# M402B.net
KiCad netlist of a schematic drawn in EAGLE
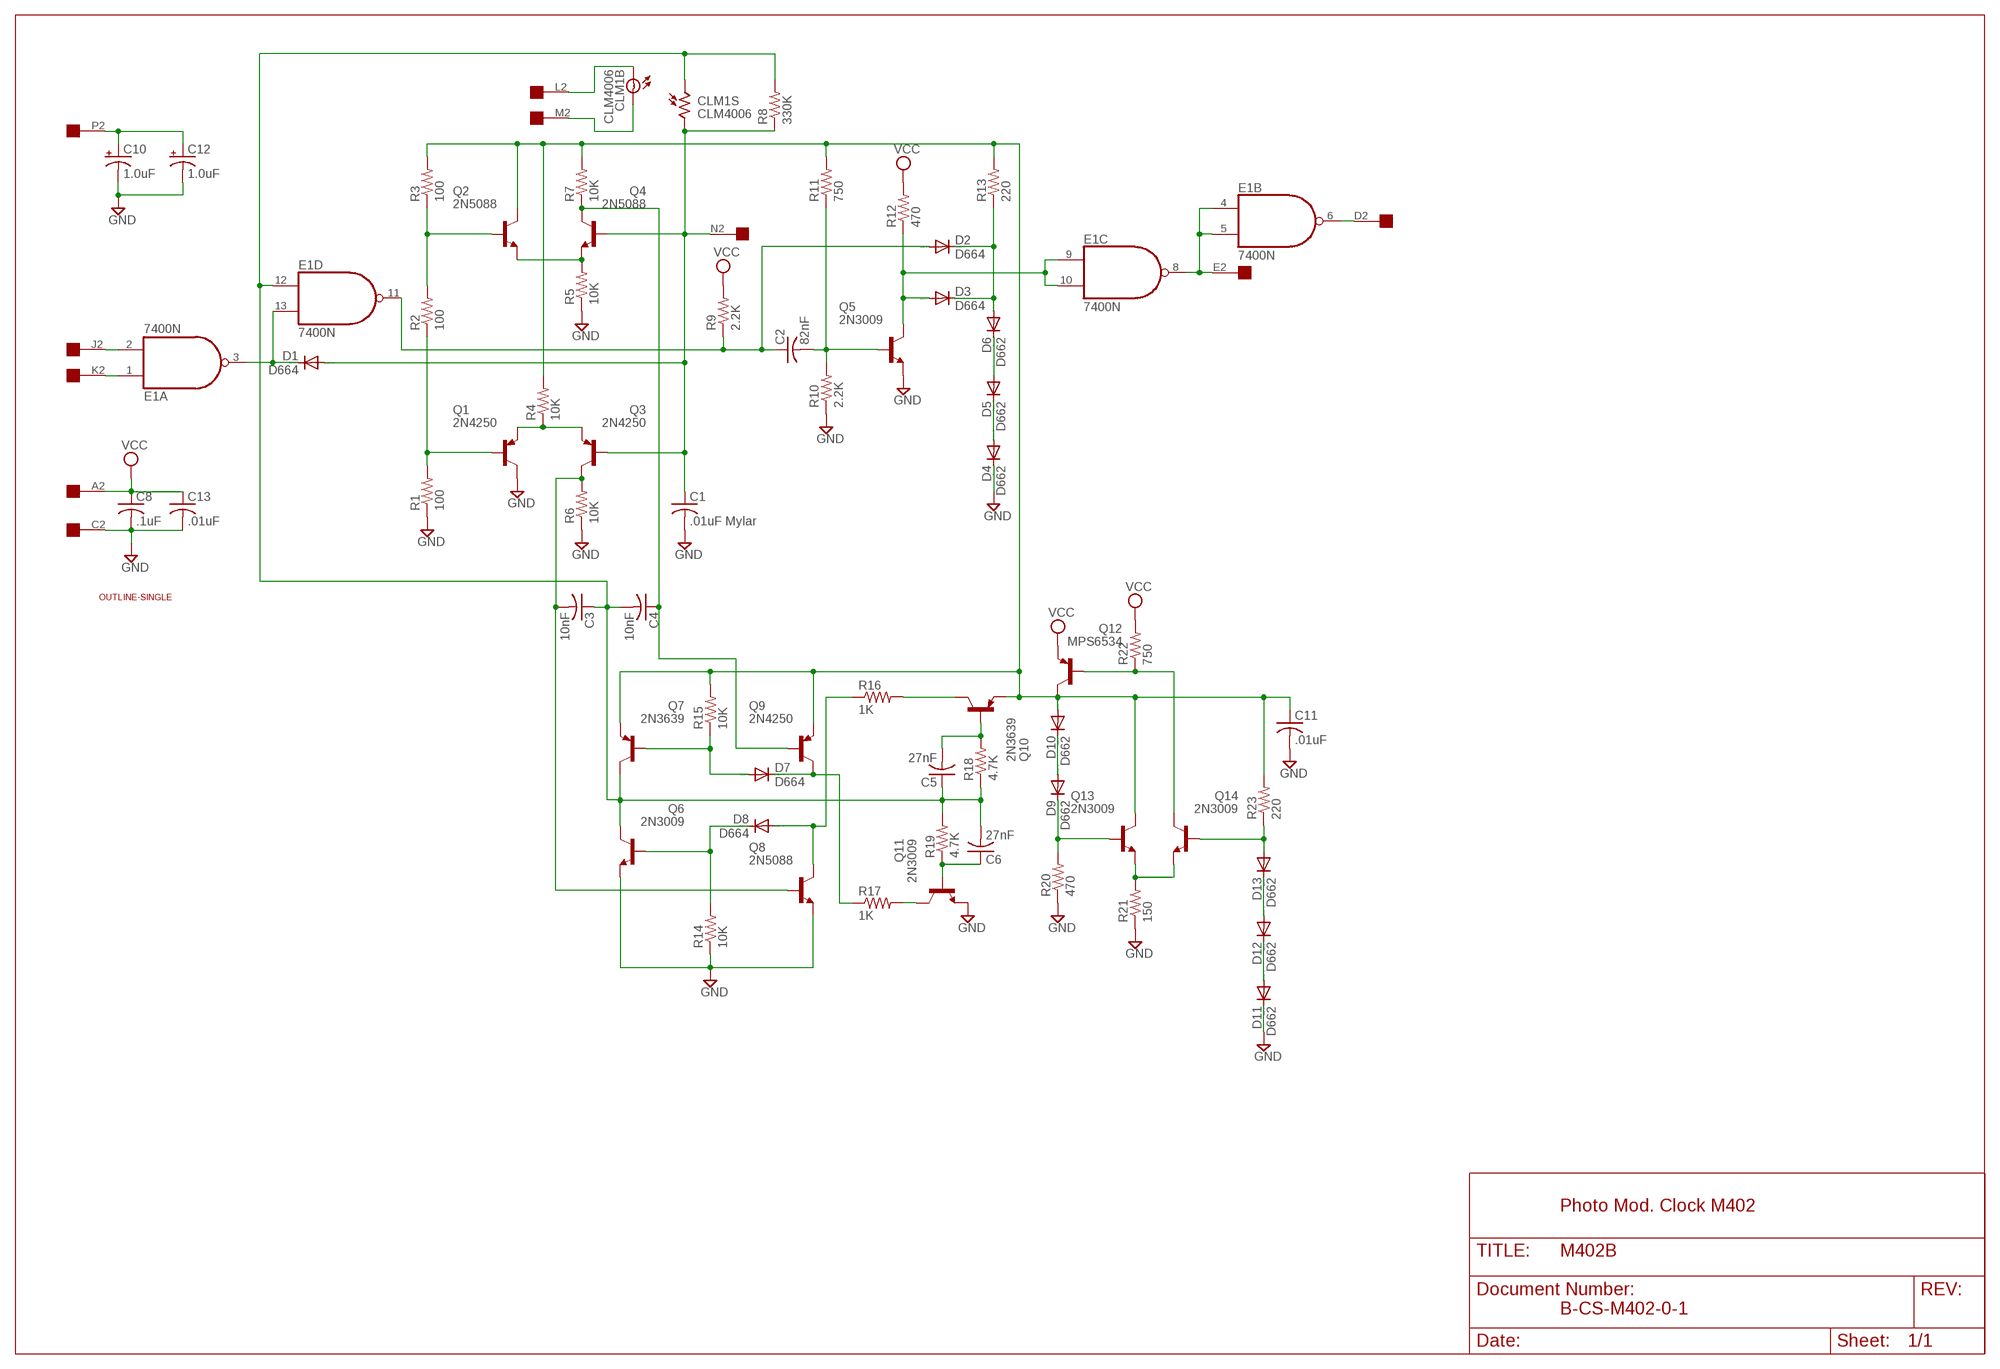
[diagram p0: schematic, sheet 1]

(export (version "E")
  (design (tool "Eeschema 10.0.6"))
  (components
    (comp (ref "C1")
      (value ".01uF Mylar")
      (footprint "eagle-import:C225-062X268")
      (libsource (lib "eagle-import") (part "C-US225-062X268"))
    )
    (comp (ref "C2")
      (value "82nF")
      (footprint "eagle-import:C050-025X075")
      (libsource (lib "eagle-import") (part "C-US050-025X075"))
    )
    (comp (ref "C3")
      (value "10nF")
      (footprint "eagle-import:C075-032X103")
      (libsource (lib "eagle-import") (part "C-US075-032X103"))
    )
    (comp (ref "C4")
      (value "10nF")
      (footprint "eagle-import:C075-032X103")
      (libsource (lib "eagle-import") (part "C-US075-032X103"))
    )
    (comp (ref "C5")
      (value "27nF")
      (footprint "eagle-import:C075-032X103")
      (libsource (lib "eagle-import") (part "C-US075-032X103"))
    )
    (comp (ref "C6")
      (value "27nF")
      (footprint "eagle-import:C075-032X103")
      (libsource (lib "eagle-import") (part "C-US075-032X103"))
    )
    (comp (ref "C8")
      (value ".1uF")
      (footprint "eagle-import:C075-032X103")
      (libsource (lib "eagle-import") (part "C-US075-032X103"))
    )
    (comp (ref "C10")
      (value "1.0uF")
      (footprint "eagle-import:E15-5")
      (libsource (lib "eagle-import") (part "CPOL-USE15-5AXIAL"))
    )
    (comp (ref "C11")
      (value ".01uF")
      (footprint "eagle-import:C050-025X075")
      (libsource (lib "eagle-import") (part "C-US050-025X075"))
    )
    (comp (ref "C12")
      (value "1.0uF")
      (footprint "eagle-import:E15-5")
      (libsource (lib "eagle-import") (part "CPOL-USE15-5AXIAL"))
    )
    (comp (ref "C13")
      (value ".01uF")
      (footprint "eagle-import:C102-043X133")
      (libsource (lib "eagle-import") (part "C-US102-043X133"))
    )
    (comp (ref "CLM1")
      (value "CLM4006")
      (footprint "eagle-import:CLM4006")
      (libsource (lib "eagle-import") (part "CLM4006"))
    )
    (comp (ref "D1")
      (value "D664")
      (footprint "eagle-import:DO35-10")
      (libsource (lib "eagle-import") (part "DIODE-DO35-10"))
    )
    (comp (ref "D2")
      (value "D664")
      (footprint "eagle-import:DO35-10")
      (libsource (lib "eagle-import") (part "DIODE-DO35-10"))
    )
    (comp (ref "D3")
      (value "D664")
      (footprint "eagle-import:DO35-10")
      (libsource (lib "eagle-import") (part "DIODE-DO35-10"))
    )
    (comp (ref "D4")
      (value "D662")
      (footprint "eagle-import:DO35-10")
      (libsource (lib "eagle-import") (part "DIODE-DO35-10"))
    )
    (comp (ref "D5")
      (value "D662")
      (footprint "eagle-import:DO35-10")
      (libsource (lib "eagle-import") (part "DIODE-DO35-10"))
    )
    (comp (ref "D6")
      (value "D662")
      (footprint "eagle-import:DO35-10")
      (libsource (lib "eagle-import") (part "DIODE-DO35-10"))
    )
    (comp (ref "D7")
      (value "D664")
      (footprint "eagle-import:DO35-10")
      (libsource (lib "eagle-import") (part "DIODE-DO35-10"))
    )
    (comp (ref "D8")
      (value "D664")
      (footprint "eagle-import:DO35-10")
      (libsource (lib "eagle-import") (part "DIODE-DO35-10"))
    )
    (comp (ref "D9")
      (value "D662")
      (footprint "eagle-import:DO35-10")
      (libsource (lib "eagle-import") (part "DIODE-DO35-10"))
    )
    (comp (ref "D10")
      (value "D662")
      (footprint "eagle-import:DO35-10")
      (libsource (lib "eagle-import") (part "DIODE-DO35-10"))
    )
    (comp (ref "D11")
      (value "D662")
      (footprint "eagle-import:DO35-10")
      (libsource (lib "eagle-import") (part "DIODE-DO35-10"))
    )
    (comp (ref "D12")
      (value "D662")
      (footprint "eagle-import:DO35-10")
      (libsource (lib "eagle-import") (part "DIODE-DO35-10"))
    )
    (comp (ref "D13")
      (value "D662")
      (footprint "eagle-import:DO35-10")
      (libsource (lib "eagle-import") (part "DIODE-DO35-10"))
    )
    (comp (ref "E1")
      (value "7400N")
      (footprint "eagle-import:DIL14")
      (libsource (lib "eagle-import") (part "7400N"))
    )
    (comp (ref "Q1")
      (value "2N4250")
      (footprint "eagle-import:TO5")
      (libsource (lib "eagle-import") (part "-PNP-TO5"))
    )
    (comp (ref "Q2")
      (value "2N5088")
      (footprint "eagle-import:TO5")
      (libsource (lib "eagle-import") (part "-NPN-TO5"))
    )
    (comp (ref "Q3")
      (value "2N4250")
      (footprint "eagle-import:TO5")
      (libsource (lib "eagle-import") (part "-PNP-TO5"))
    )
    (comp (ref "Q4")
      (value "2N5088")
      (footprint "eagle-import:TO5")
      (libsource (lib "eagle-import") (part "-NPN-TO5"))
    )
    (comp (ref "Q5")
      (value "2N3009")
      (footprint "eagle-import:TO5")
      (libsource (lib "eagle-import") (part "-NPN-TO5"))
    )
    (comp (ref "Q6")
      (value "2N3009")
      (footprint "eagle-import:TO5")
      (libsource (lib "eagle-import") (part "-NPN-TO5"))
    )
    (comp (ref "Q7")
      (value "2N3639")
      (footprint "eagle-import:TO5")
      (libsource (lib "eagle-import") (part "-PNP-TO5"))
    )
    (comp (ref "Q8")
      (value "2N5088")
      (footprint "eagle-import:TO5")
      (libsource (lib "eagle-import") (part "-NPN-TO5"))
    )
    (comp (ref "Q9")
      (value "2N4250")
      (footprint "eagle-import:TO5")
      (libsource (lib "eagle-import") (part "-PNP-TO5"))
    )
    (comp (ref "Q10")
      (value "2N3639")
      (footprint "eagle-import:TO5")
      (libsource (lib "eagle-import") (part "-PNP-TO5"))
    )
    (comp (ref "Q11")
      (value "2N3009")
      (footprint "eagle-import:TO5")
      (libsource (lib "eagle-import") (part "-NPN-TO5"))
    )
    (comp (ref "Q12")
      (value "MPS6534")
      (footprint "eagle-import:TO5")
      (libsource (lib "eagle-import") (part "-PNP-TO5"))
    )
    (comp (ref "Q13")
      (value "2N3009")
      (footprint "eagle-import:TO5")
      (libsource (lib "eagle-import") (part "-NPN-TO5"))
    )
    (comp (ref "Q14")
      (value "2N3009")
      (footprint "eagle-import:TO5")
      (libsource (lib "eagle-import") (part "-NPN-TO5"))
    )
    (comp (ref "R1")
      (value "100")
      (footprint "eagle-import:0207_10")
      (libsource (lib "eagle-import") (part "R-US_0207/10"))
    )
    (comp (ref "R2")
      (value "100")
      (footprint "eagle-import:0207_10")
      (libsource (lib "eagle-import") (part "R-US_0207/10"))
    )
    (comp (ref "R3")
      (value "100")
      (footprint "eagle-import:0207_10")
      (libsource (lib "eagle-import") (part "R-US_0207/10"))
    )
    (comp (ref "R4")
      (value "10K")
      (footprint "eagle-import:0207_10")
      (libsource (lib "eagle-import") (part "R-US_0207/10"))
    )
    (comp (ref "R5")
      (value "10K")
      (footprint "eagle-import:0207_10")
      (libsource (lib "eagle-import") (part "R-US_0207/10"))
    )
    (comp (ref "R6")
      (value "10K")
      (footprint "eagle-import:0207_10")
      (libsource (lib "eagle-import") (part "R-US_0207/10"))
    )
    (comp (ref "R7")
      (value "10K")
      (footprint "eagle-import:0207_10")
      (libsource (lib "eagle-import") (part "R-US_0207/10"))
    )
    (comp (ref "R8")
      (value "330K")
      (footprint "eagle-import:0207_10")
      (libsource (lib "eagle-import") (part "R-US_0207/10"))
    )
    (comp (ref "R9")
      (value "2.2K")
      (footprint "eagle-import:0207_10")
      (libsource (lib "eagle-import") (part "R-US_0207/10"))
    )
    (comp (ref "R10")
      (value "2.2K")
      (footprint "eagle-import:0207_10")
      (libsource (lib "eagle-import") (part "R-US_0207/10"))
    )
    (comp (ref "R11")
      (value "750")
      (footprint "eagle-import:0207_10")
      (libsource (lib "eagle-import") (part "R-US_0207/10"))
    )
    (comp (ref "R12")
      (value "470")
      (footprint "eagle-import:0207_10")
      (libsource (lib "eagle-import") (part "R-US_0207/10"))
    )
    (comp (ref "R13")
      (value "220")
      (footprint "eagle-import:0207_10")
      (libsource (lib "eagle-import") (part "R-US_0207/10"))
    )
    (comp (ref "R14")
      (value "10K")
      (footprint "eagle-import:0207_10")
      (libsource (lib "eagle-import") (part "R-US_0207/10"))
    )
    (comp (ref "R15")
      (value "10K")
      (footprint "eagle-import:0207_10")
      (libsource (lib "eagle-import") (part "R-US_0207/10"))
    )
    (comp (ref "R16")
      (value "1K")
      (footprint "eagle-import:0207_10")
      (libsource (lib "eagle-import") (part "R-US_0207/10"))
    )
    (comp (ref "R17")
      (value "1K")
      (footprint "eagle-import:0207_10")
      (libsource (lib "eagle-import") (part "R-US_0207/10"))
    )
    (comp (ref "R18")
      (value "4.7K")
      (footprint "eagle-import:0207_10")
      (libsource (lib "eagle-import") (part "R-US_0207/10"))
    )
    (comp (ref "R19")
      (value "4.7K")
      (footprint "eagle-import:0207_10")
      (libsource (lib "eagle-import") (part "R-US_0207/10"))
    )
    (comp (ref "R20")
      (value "470")
      (footprint "eagle-import:0207_10")
      (libsource (lib "eagle-import") (part "R-US_0207/10"))
    )
    (comp (ref "R21")
      (value "150")
      (footprint "eagle-import:0207_10")
      (libsource (lib "eagle-import") (part "R-US_0207/10"))
    )
    (comp (ref "R22")
      (value "750")
      (footprint "eagle-import:0207_10")
      (libsource (lib "eagle-import") (part "R-US_0207/10"))
    )
    (comp (ref "R23")
      (value "220")
      (footprint "eagle-import:0207_10")
      (libsource (lib "eagle-import") (part "R-US_0207/10"))
    )
    (comp (ref "U$1")
      (value "OUTLINE-SINGLE")
      (footprint "eagle-import:SINGLE")
      (libsource (lib "eagle-import") (part "OUTLINE-SINGLE"))
    )
    (comp (ref "U$3")
      (value "EDGE-1")
      (footprint "eagle-import:EDGE-CON1")
      (libsource (lib "eagle-import") (part "EDGE-1"))
    )
  )
  (nets
    (net (code "1") (name "GND") (class "Default")
      (node (ref "C1") (pin "2") (pinfunction "2_2") (pintype "passive"))
      (node (ref "C10") (pin "-") (pinfunction "-_-") (pintype "passive"))
      (node (ref "C11") (pin "2") (pinfunction "2_2") (pintype "passive"))
      (node (ref "C12") (pin "-") (pinfunction "-_-") (pintype "passive"))
      (node (ref "C13") (pin "2") (pinfunction "2_2") (pintype "passive"))
      (node (ref "C8") (pin "2") (pinfunction "2_2") (pintype "passive"))
      (node (ref "D11") (pin "C") (pinfunction "C_C") (pintype "passive"))
      (node (ref "D4") (pin "C") (pinfunction "C_C") (pintype "passive"))
      (node (ref "Q1") (pin "3") (pinfunction "C_3") (pintype "passive"))
      (node (ref "Q11") (pin "1") (pinfunction "E_1") (pintype "passive"))
      (node (ref "Q5") (pin "1") (pinfunction "E_1") (pintype "passive"))
      (node (ref "Q6") (pin "1") (pinfunction "E_1") (pintype "passive"))
      (node (ref "Q8") (pin "1") (pinfunction "E_1") (pintype "passive"))
      (node (ref "R1") (pin "1") (pinfunction "1_1") (pintype "passive"))
      (node (ref "R10") (pin "1") (pinfunction "1_1") (pintype "passive"))
      (node (ref "R14") (pin "1") (pinfunction "1_1") (pintype "passive"))
      (node (ref "R20") (pin "1") (pinfunction "1_1") (pintype "passive"))
      (node (ref "R21") (pin "1") (pinfunction "1_1") (pintype "passive"))
      (node (ref "R5") (pin "1") (pinfunction "1_1") (pintype "passive"))
      (node (ref "R6") (pin "1") (pinfunction "1_1") (pintype "passive"))
      (node (ref "U$3") (pin "C2") (pinfunction "1_C2") (pintype "bidirectional"))
    )
    (net (code "2") (name "Net-(CLM1A-A)") (class "Default")
      (node (ref "CLM1") (pin "B1") (pinfunction "A_B1") (pintype "passive"))
      (node (ref "U$3") (pin "M2") (pinfunction "1_M2") (pintype "bidirectional"))
    )
    (net (code "3") (name "Net-(CLM1A-B)") (class "Default")
      (node (ref "CLM1") (pin "B2") (pinfunction "B_B2") (pintype "passive"))
      (node (ref "U$3") (pin "L2") (pinfunction "1_L2") (pintype "bidirectional"))
    )
    (net (code "4") (name "Net-(CLM1B-1)") (class "Default")
      (node (ref "C3") (pin "1") (pinfunction "1_1") (pintype "passive"))
      (node (ref "C4") (pin "2") (pinfunction "2_2") (pintype "passive"))
      (node (ref "C5") (pin "1") (pinfunction "1_1") (pintype "passive"))
      (node (ref "C6") (pin "2") (pinfunction "2_2") (pintype "passive"))
      (node (ref "CLM1") (pin "S1") (pinfunction "1_S1") (pintype "passive"))
      (node (ref "E1") (pin "12") (pinfunction "I0_12") (pintype "input"))
      (node (ref "Q6") (pin "3") (pinfunction "C_3") (pintype "passive"))
      (node (ref "Q7") (pin "3") (pinfunction "C_3") (pintype "passive"))
      (node (ref "R18") (pin "1") (pinfunction "1_1") (pintype "passive"))
      (node (ref "R19") (pin "2") (pinfunction "2_2") (pintype "passive"))
      (node (ref "R8") (pin "2") (pinfunction "2_2") (pintype "passive"))
    )
    (net (code "5") (name "Net-(CLM1B-2)") (class "Default")
      (node (ref "C1") (pin "1") (pinfunction "1_1") (pintype "passive"))
      (node (ref "CLM1") (pin "S2") (pinfunction "2_S2") (pintype "passive"))
      (node (ref "D1") (pin "A") (pinfunction "A_A") (pintype "passive"))
      (node (ref "Q3") (pin "2") (pinfunction "B_2") (pintype "passive"))
      (node (ref "Q4") (pin "2") (pinfunction "B_2") (pintype "passive"))
      (node (ref "R8") (pin "1") (pinfunction "1_1") (pintype "passive"))
      (node (ref "U$3") (pin "N2") (pinfunction "1_N2") (pintype "bidirectional"))
    )
    (net (code "6") (name "Net-(D2-PadC)") (class "Default")
      (node (ref "D2") (pin "C") (pinfunction "C_C") (pintype "passive"))
      (node (ref "D3") (pin "C") (pinfunction "C_C") (pintype "passive"))
      (node (ref "D6") (pin "A") (pinfunction "A_A") (pintype "passive"))
      (node (ref "R13") (pin "1") (pinfunction "1_1") (pintype "passive"))
    )
    (net (code "7") (name "Net-(D4-PadA)") (class "Default")
      (node (ref "D4") (pin "A") (pinfunction "A_A") (pintype "passive"))
      (node (ref "D5") (pin "C") (pinfunction "C_C") (pintype "passive"))
    )
    (net (code "8") (name "Net-(D5-PadA)") (class "Default")
      (node (ref "D5") (pin "A") (pinfunction "A_A") (pintype "passive"))
      (node (ref "D6") (pin "C") (pinfunction "C_C") (pintype "passive"))
    )
    (net (code "9") (name "Net-(D10-PadC)") (class "Default")
      (node (ref "D10") (pin "C") (pinfunction "C_C") (pintype "passive"))
      (node (ref "D9") (pin "A") (pinfunction "A_A") (pintype "passive"))
    )
    (net (code "10") (name "Net-(D11-PadA)") (class "Default")
      (node (ref "D11") (pin "A") (pinfunction "A_A") (pintype "passive"))
      (node (ref "D12") (pin "C") (pinfunction "C_C") (pintype "passive"))
    )
    (net (code "11") (name "Net-(D12-PadA)") (class "Default")
      (node (ref "D12") (pin "A") (pinfunction "A_A") (pintype "passive"))
      (node (ref "D13") (pin "C") (pinfunction "C_C") (pintype "passive"))
    )
    (net (code "12") (name "Net-(E1A-I0)") (class "Default")
      (node (ref "E1") (pin "1") (pinfunction "I0_1") (pintype "input"))
      (node (ref "U$3") (pin "K2") (pinfunction "1_K2") (pintype "bidirectional"))
    )
    (net (code "13") (name "Net-(E1A-I1)") (class "Default")
      (node (ref "E1") (pin "2") (pinfunction "I1_2") (pintype "input"))
      (node (ref "U$3") (pin "J2") (pinfunction "1_J2") (pintype "bidirectional"))
    )
    (net (code "14") (name "Net-(E1A-O)") (class "Default")
      (node (ref "D1") (pin "C") (pinfunction "C_C") (pintype "passive"))
      (node (ref "E1") (pin "13") (pinfunction "I1_13") (pintype "input"))
      (node (ref "E1") (pin "3") (pinfunction "O_3") (pintype "output"))
    )
    (net (code "15") (name "Net-(E1B-I0)") (class "Default")
      (node (ref "E1") (pin "4") (pinfunction "I0_4") (pintype "input"))
      (node (ref "E1") (pin "5") (pinfunction "I1_5") (pintype "input"))
      (node (ref "E1") (pin "8") (pinfunction "O_8") (pintype "output"))
      (node (ref "U$3") (pin "E2") (pinfunction "1_E2") (pintype "bidirectional"))
    )
    (net (code "16") (name "Net-(E1B-O)") (class "Default")
      (node (ref "E1") (pin "6") (pinfunction "O_6") (pintype "output"))
      (node (ref "U$3") (pin "D2") (pinfunction "1_D2") (pintype "bidirectional"))
    )
    (net (code "17") (name "Net-(E1C-I0)") (class "Default")
      (node (ref "D3") (pin "A") (pinfunction "A_A") (pintype "passive"))
      (node (ref "E1") (pin "10") (pinfunction "I1_10") (pintype "input"))
      (node (ref "E1") (pin "9") (pinfunction "I0_9") (pintype "input"))
      (node (ref "Q5") (pin "3") (pinfunction "C_3") (pintype "passive"))
      (node (ref "R12") (pin "1") (pinfunction "1_1") (pintype "passive"))
    )
    (net (code "18") (name "Net-(E1D-O)") (class "Default")
      (node (ref "C2") (pin "1") (pinfunction "1_1") (pintype "passive"))
      (node (ref "D2") (pin "A") (pinfunction "A_A") (pintype "passive"))
      (node (ref "E1") (pin "11") (pinfunction "O_11") (pintype "output"))
      (node (ref "R9") (pin "1") (pinfunction "1_1") (pintype "passive"))
    )
    (net (code "19") (name "Net-(Q1-B)") (class "Default")
      (node (ref "Q1") (pin "2") (pinfunction "B_2") (pintype "passive"))
      (node (ref "R1") (pin "2") (pinfunction "2_2") (pintype "passive"))
      (node (ref "R2") (pin "1") (pinfunction "1_1") (pintype "passive"))
    )
    (net (code "20") (name "Net-(Q1-E)") (class "Default")
      (node (ref "Q1") (pin "1") (pinfunction "E_1") (pintype "passive"))
      (node (ref "Q3") (pin "1") (pinfunction "E_1") (pintype "passive"))
      (node (ref "R4") (pin "1") (pinfunction "1_1") (pintype "passive"))
    )
    (net (code "21") (name "Net-(Q2-B)") (class "Default")
      (node (ref "Q2") (pin "2") (pinfunction "B_2") (pintype "passive"))
      (node (ref "R2") (pin "2") (pinfunction "2_2") (pintype "passive"))
      (node (ref "R3") (pin "1") (pinfunction "1_1") (pintype "passive"))
    )
    (net (code "22") (name "Net-(Q2-E)") (class "Default")
      (node (ref "Q2") (pin "1") (pinfunction "E_1") (pintype "passive"))
      (node (ref "Q4") (pin "1") (pinfunction "E_1") (pintype "passive"))
      (node (ref "R5") (pin "2") (pinfunction "2_2") (pintype "passive"))
    )
    (net (code "23") (name "Net-(Q3-C)") (class "Default")
      (node (ref "C3") (pin "2") (pinfunction "2_2") (pintype "passive"))
      (node (ref "Q3") (pin "3") (pinfunction "C_3") (pintype "passive"))
      (node (ref "Q8") (pin "2") (pinfunction "B_2") (pintype "passive"))
      (node (ref "R6") (pin "2") (pinfunction "2_2") (pintype "passive"))
    )
    (net (code "24") (name "Net-(Q4-C)") (class "Default")
      (node (ref "C4") (pin "1") (pinfunction "1_1") (pintype "passive"))
      (node (ref "Q4") (pin "3") (pinfunction "C_3") (pintype "passive"))
      (node (ref "Q9") (pin "2") (pinfunction "B_2") (pintype "passive"))
      (node (ref "R7") (pin "1") (pinfunction "1_1") (pintype "passive"))
    )
    (net (code "25") (name "Net-(Q5-B)") (class "Default")
      (node (ref "C2") (pin "2") (pinfunction "2_2") (pintype "passive"))
      (node (ref "Q5") (pin "2") (pinfunction "B_2") (pintype "passive"))
      (node (ref "R10") (pin "2") (pinfunction "2_2") (pintype "passive"))
      (node (ref "R11") (pin "1") (pinfunction "1_1") (pintype "passive"))
    )
    (net (code "26") (name "Net-(Q6-B)") (class "Default")
      (node (ref "D8") (pin "C") (pinfunction "C_C") (pintype "passive"))
      (node (ref "Q6") (pin "2") (pinfunction "B_2") (pintype "passive"))
      (node (ref "R14") (pin "2") (pinfunction "2_2") (pintype "passive"))
    )
    (net (code "27") (name "Net-(Q7-B)") (class "Default")
      (node (ref "D7") (pin "A") (pinfunction "A_A") (pintype "passive"))
      (node (ref "Q7") (pin "2") (pinfunction "B_2") (pintype "passive"))
      (node (ref "R15") (pin "1") (pinfunction "1_1") (pintype "passive"))
    )
    (net (code "28") (name "Net-(Q8-C)") (class "Default")
      (node (ref "D8") (pin "A") (pinfunction "A_A") (pintype "passive"))
      (node (ref "Q8") (pin "3") (pinfunction "C_3") (pintype "passive"))
      (node (ref "R16") (pin "1") (pinfunction "1_1") (pintype "passive"))
    )
    (net (code "29") (name "Net-(Q9-C)") (class "Default")
      (node (ref "D7") (pin "C") (pinfunction "C_C") (pintype "passive"))
      (node (ref "Q9") (pin "3") (pinfunction "C_3") (pintype "passive"))
      (node (ref "R17") (pin "1") (pinfunction "1_1") (pintype "passive"))
    )
    (net (code "30") (name "Net-(Q10-B)") (class "Default")
      (node (ref "C5") (pin "2") (pinfunction "2_2") (pintype "passive"))
      (node (ref "Q10") (pin "2") (pinfunction "B_2") (pintype "passive"))
      (node (ref "R18") (pin "2") (pinfunction "2_2") (pintype "passive"))
    )
    (net (code "31") (name "Net-(Q10-C)") (class "Default")
      (node (ref "Q10") (pin "3") (pinfunction "C_3") (pintype "passive"))
      (node (ref "R16") (pin "2") (pinfunction "2_2") (pintype "passive"))
    )
    (net (code "32") (name "Net-(Q10-E)") (class "Default")
      (node (ref "C11") (pin "1") (pinfunction "1_1") (pintype "passive"))
      (node (ref "D10") (pin "A") (pinfunction "A_A") (pintype "passive"))
      (node (ref "Q10") (pin "1") (pinfunction "E_1") (pintype "passive"))
      (node (ref "Q12") (pin "3") (pinfunction "C_3") (pintype "passive"))
      (node (ref "Q13") (pin "3") (pinfunction "C_3") (pintype "passive"))
      (node (ref "Q2") (pin "3") (pinfunction "C_3") (pintype "passive"))
      (node (ref "Q7") (pin "1") (pinfunction "E_1") (pintype "passive"))
      (node (ref "Q9") (pin "1") (pinfunction "E_1") (pintype "passive"))
      (node (ref "R11") (pin "2") (pinfunction "2_2") (pintype "passive"))
      (node (ref "R13") (pin "2") (pinfunction "2_2") (pintype "passive"))
      (node (ref "R15") (pin "2") (pinfunction "2_2") (pintype "passive"))
      (node (ref "R23") (pin "2") (pinfunction "2_2") (pintype "passive"))
      (node (ref "R3") (pin "2") (pinfunction "2_2") (pintype "passive"))
      (node (ref "R4") (pin "2") (pinfunction "2_2") (pintype "passive"))
      (node (ref "R7") (pin "2") (pinfunction "2_2") (pintype "passive"))
    )
    (net (code "33") (name "Net-(Q11-B)") (class "Default")
      (node (ref "C6") (pin "1") (pinfunction "1_1") (pintype "passive"))
      (node (ref "Q11") (pin "2") (pinfunction "B_2") (pintype "passive"))
      (node (ref "R19") (pin "1") (pinfunction "1_1") (pintype "passive"))
    )
    (net (code "34") (name "Net-(Q11-C)") (class "Default")
      (node (ref "Q11") (pin "3") (pinfunction "C_3") (pintype "passive"))
      (node (ref "R17") (pin "2") (pinfunction "2_2") (pintype "passive"))
    )
    (net (code "35") (name "Net-(Q12-B)") (class "Default")
      (node (ref "Q12") (pin "2") (pinfunction "B_2") (pintype "passive"))
      (node (ref "Q14") (pin "3") (pinfunction "C_3") (pintype "passive"))
      (node (ref "R22") (pin "1") (pinfunction "1_1") (pintype "passive"))
    )
    (net (code "36") (name "Net-(Q13-B)") (class "Default")
      (node (ref "D9") (pin "C") (pinfunction "C_C") (pintype "passive"))
      (node (ref "Q13") (pin "2") (pinfunction "B_2") (pintype "passive"))
      (node (ref "R20") (pin "2") (pinfunction "2_2") (pintype "passive"))
    )
    (net (code "37") (name "Net-(Q13-E)") (class "Default")
      (node (ref "Q13") (pin "1") (pinfunction "E_1") (pintype "passive"))
      (node (ref "Q14") (pin "1") (pinfunction "E_1") (pintype "passive"))
      (node (ref "R21") (pin "2") (pinfunction "2_2") (pintype "passive"))
    )
    (net (code "38") (name "Net-(Q14-B)") (class "Default")
      (node (ref "D13") (pin "A") (pinfunction "A_A") (pintype "passive"))
      (node (ref "Q14") (pin "2") (pinfunction "B_2") (pintype "passive"))
      (node (ref "R23") (pin "1") (pinfunction "1_1") (pintype "passive"))
    )
    (net (code "39") (name "Net-(U$3M-1)") (class "Default")
      (node (ref "C10") (pin "+") (pinfunction "+_+") (pintype "passive"))
      (node (ref "C12") (pin "+") (pinfunction "+_+") (pintype "passive"))
      (node (ref "U$3") (pin "P2") (pinfunction "1_P2") (pintype "bidirectional"))
    )
    (net (code "40") (name "VCC") (class "Default")
      (node (ref "C13") (pin "1") (pinfunction "1_1") (pintype "passive"))
      (node (ref "C8") (pin "1") (pinfunction "1_1") (pintype "passive"))
      (node (ref "Q12") (pin "1") (pinfunction "E_1") (pintype "passive"))
      (node (ref "R12") (pin "2") (pinfunction "2_2") (pintype "passive"))
      (node (ref "R22") (pin "2") (pinfunction "2_2") (pintype "passive"))
      (node (ref "R9") (pin "2") (pinfunction "2_2") (pintype "passive"))
      (node (ref "U$3") (pin "A2") (pinfunction "1_A2") (pintype "bidirectional"))
    )
  )
)
